# Crumb_Adapter_V1_2.net
KiCad netlist of a schematic drawn in EAGLE
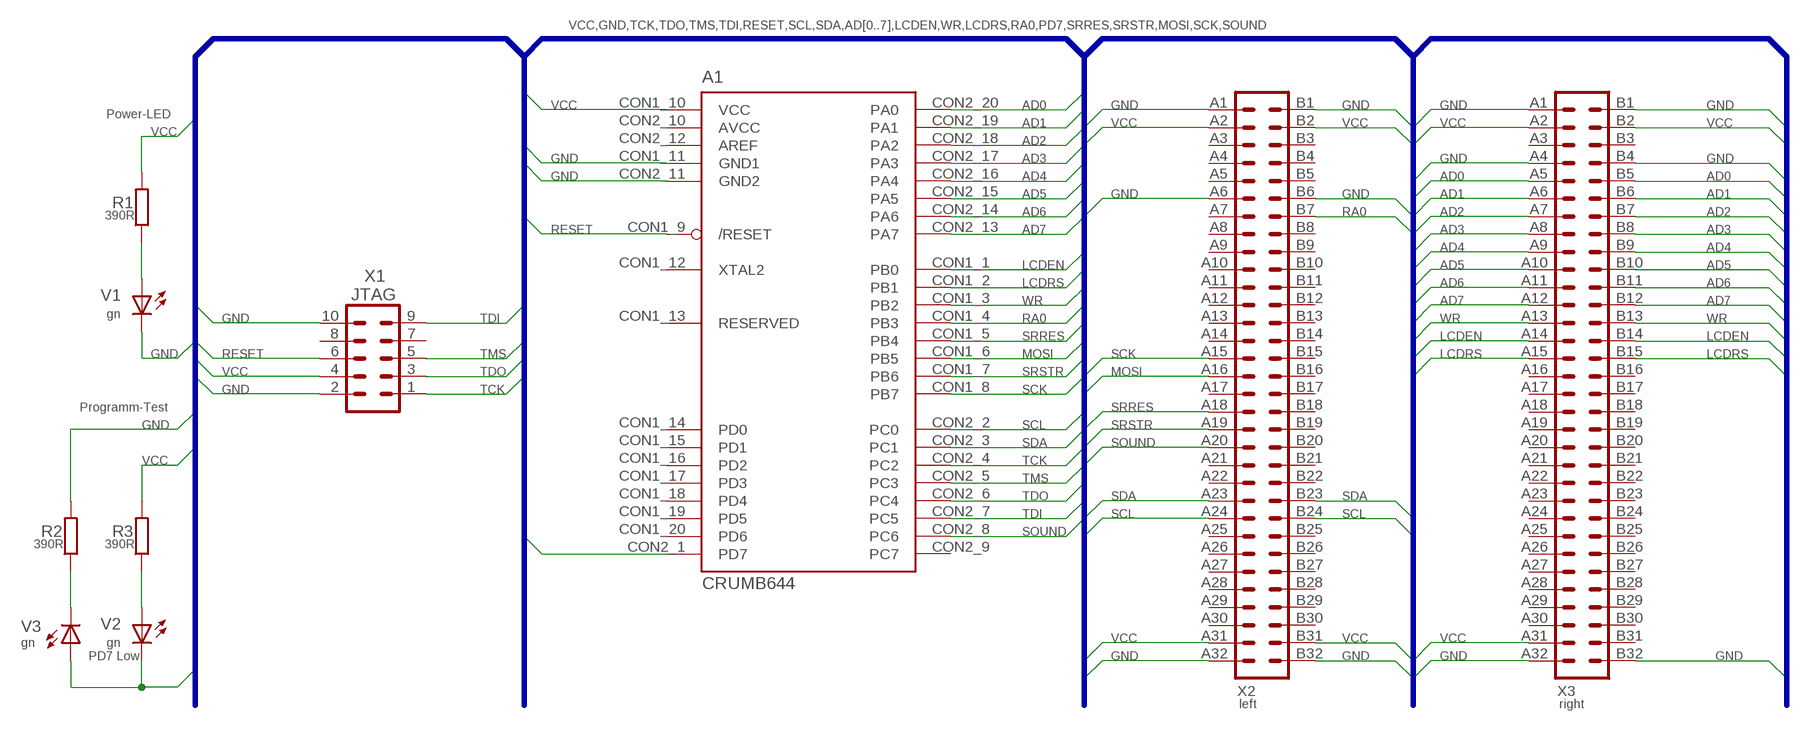
[diagram p0: schematic, sheet 1]

(export (version "E")
  (design (tool "Eeschema 10.0.6"))
  (components
    (comp (ref "A1")
      (value "CRUMB644")
      (footprint "eagle-import:CRUMB644")
      (libsource (lib "eagle-import") (part "CRUMB644"))
    )
    (comp (ref "R1")
      (value "390R")
      (footprint "eagle-import:M1206")
      (libsource (lib "eagle-import") (part "R-EU_VM1206"))
    )
    (comp (ref "R2")
      (value "390R")
      (footprint "eagle-import:M1206")
      (libsource (lib "eagle-import") (part "R-EU_VM1206"))
    )
    (comp (ref "R3")
      (value "390R")
      (footprint "eagle-import:M1206")
      (libsource (lib "eagle-import") (part "R-EU_VM1206"))
    )
    (comp (ref "V1")
      (value "gn")
      (footprint "eagle-import:CHIPLED_1206")
      (libsource (lib "eagle-import") (part "LEDCHIPLED_1206"))
    )
    (comp (ref "V2")
      (value "gn")
      (footprint "eagle-import:CHIPLED_1206")
      (libsource (lib "eagle-import") (part "LEDCHIPLED_1206"))
    )
    (comp (ref "V3")
      (value "gn")
      (footprint "eagle-import:CHIPLED_1206")
      (libsource (lib "eagle-import") (part "LEDCHIPLED_1206"))
    )
    (comp (ref "X1")
      (value "JTAG")
      (footprint "eagle-import:MA05-2")
      (libsource (lib "eagle-import") (part "MA05-2"))
    )
    (comp (ref "X2")
      (value "left")
      (footprint "eagle-import:MAB32-2")
      (libsource (lib "eagle-import") (part "MAB64"))
    )
    (comp (ref "X3")
      (value "right")
      (footprint "eagle-import:MAB32-2")
      (libsource (lib "eagle-import") (part "MAB64"))
    )
  )
  (nets
    (net (code "1") (name "/AD0") (class "Default")
      (node (ref "A1") (pin "CON2_20") (pinfunction "PA0_CON2_20") (pintype "bidirectional"))
      (node (ref "X3") (pin "A5") (pinfunction "A5_A5") (pintype "passive"))
      (node (ref "X3") (pin "B5") (pinfunction "B5_B5") (pintype "passive"))
    )
    (net (code "2") (name "/AD1") (class "Default")
      (node (ref "A1") (pin "CON2_19") (pinfunction "PA1_CON2_19") (pintype "bidirectional"))
      (node (ref "X3") (pin "A6") (pinfunction "A6_A6") (pintype "passive"))
      (node (ref "X3") (pin "B6") (pinfunction "B6_B6") (pintype "passive"))
    )
    (net (code "3") (name "/AD2") (class "Default")
      (node (ref "A1") (pin "CON2_18") (pinfunction "PA2_CON2_18") (pintype "bidirectional"))
      (node (ref "X3") (pin "A7") (pinfunction "A7_A7") (pintype "passive"))
      (node (ref "X3") (pin "B7") (pinfunction "B7_B7") (pintype "passive"))
    )
    (net (code "4") (name "/AD3") (class "Default")
      (node (ref "A1") (pin "CON2_17") (pinfunction "PA3_CON2_17") (pintype "bidirectional"))
      (node (ref "X3") (pin "A8") (pinfunction "A8_A8") (pintype "passive"))
      (node (ref "X3") (pin "B8") (pinfunction "B8_B8") (pintype "passive"))
    )
    (net (code "5") (name "/AD4") (class "Default")
      (node (ref "A1") (pin "CON2_16") (pinfunction "PA4_CON2_16") (pintype "bidirectional"))
      (node (ref "X3") (pin "A9") (pinfunction "A9_A9") (pintype "passive"))
      (node (ref "X3") (pin "B9") (pinfunction "B9_B9") (pintype "passive"))
    )
    (net (code "6") (name "/AD5") (class "Default")
      (node (ref "A1") (pin "CON2_15") (pinfunction "PA5_CON2_15") (pintype "bidirectional"))
      (node (ref "X3") (pin "A10") (pinfunction "A10_A10") (pintype "passive"))
      (node (ref "X3") (pin "B10") (pinfunction "B10_B10") (pintype "passive"))
    )
    (net (code "7") (name "/AD6") (class "Default")
      (node (ref "A1") (pin "CON2_14") (pinfunction "PA6_CON2_14") (pintype "bidirectional"))
      (node (ref "X3") (pin "A11") (pinfunction "A11_A11") (pintype "passive"))
      (node (ref "X3") (pin "B11") (pinfunction "B11_B11") (pintype "passive"))
    )
    (net (code "8") (name "/AD7") (class "Default")
      (node (ref "A1") (pin "CON2_13") (pinfunction "PA7_CON2_13") (pintype "bidirectional"))
      (node (ref "X3") (pin "A12") (pinfunction "A12_A12") (pintype "passive"))
      (node (ref "X3") (pin "B12") (pinfunction "B12_B12") (pintype "passive"))
    )
    (net (code "9") (name "/GND") (class "Default")
      (node (ref "A1") (pin "CON1_11") (pinfunction "GND1_CON1_11") (pintype "power_in"))
      (node (ref "A1") (pin "CON2_11") (pinfunction "GND2_CON2_11") (pintype "power_in"))
      (node (ref "R2") (pin "2") (pinfunction "2_2") (pintype "passive"))
      (node (ref "V1") (pin "C") (pinfunction "C_C") (pintype "passive"))
      (node (ref "X1") (pin "10") (pinfunction "10_10") (pintype "passive"))
      (node (ref "X1") (pin "2") (pinfunction "2_2") (pintype "passive"))
      (node (ref "X2") (pin "A1") (pinfunction "A1_A1") (pintype "passive"))
      (node (ref "X2") (pin "A32") (pinfunction "A32_A32") (pintype "passive"))
      (node (ref "X2") (pin "A6") (pinfunction "A6_A6") (pintype "passive"))
      (node (ref "X2") (pin "B1") (pinfunction "B1_B1") (pintype "passive"))
      (node (ref "X2") (pin "B32") (pinfunction "B32_B32") (pintype "passive"))
      (node (ref "X2") (pin "B6") (pinfunction "B6_B6") (pintype "passive"))
      (node (ref "X3") (pin "A1") (pinfunction "A1_A1") (pintype "passive"))
      (node (ref "X3") (pin "A32") (pinfunction "A32_A32") (pintype "passive"))
      (node (ref "X3") (pin "A4") (pinfunction "A4_A4") (pintype "passive"))
      (node (ref "X3") (pin "B1") (pinfunction "B1_B1") (pintype "passive"))
      (node (ref "X3") (pin "B32") (pinfunction "B32_B32") (pintype "passive"))
      (node (ref "X3") (pin "B4") (pinfunction "B4_B4") (pintype "passive"))
    )
    (net (code "10") (name "/LCDEN") (class "Default")
      (node (ref "A1") (pin "CON1_1") (pinfunction "PB0_CON1_1") (pintype "bidirectional"))
      (node (ref "X3") (pin "A14") (pinfunction "A14_A14") (pintype "passive"))
      (node (ref "X3") (pin "B14") (pinfunction "B14_B14") (pintype "passive"))
    )
    (net (code "11") (name "/LCDRS") (class "Default")
      (node (ref "A1") (pin "CON1_2") (pinfunction "PB1_CON1_2") (pintype "bidirectional"))
      (node (ref "X3") (pin "A15") (pinfunction "A15_A15") (pintype "passive"))
      (node (ref "X3") (pin "B15") (pinfunction "B15_B15") (pintype "passive"))
    )
    (net (code "12") (name "/MOSI") (class "Default")
      (node (ref "A1") (pin "CON1_6") (pinfunction "PB5_CON1_6") (pintype "bidirectional"))
      (node (ref "X2") (pin "A16") (pinfunction "A16_A16") (pintype "passive"))
    )
    (net (code "13") (name "/PD7") (class "Default")
      (node (ref "A1") (pin "CON2_1") (pinfunction "PD7_CON2_1") (pintype "bidirectional"))
      (node (ref "V2") (pin "C") (pinfunction "C_C") (pintype "passive"))
      (node (ref "V3") (pin "A") (pinfunction "A_A") (pintype "passive"))
    )
    (net (code "14") (name "/RA0") (class "Default")
      (node (ref "A1") (pin "CON1_4") (pinfunction "PB3_CON1_4") (pintype "bidirectional"))
      (node (ref "X2") (pin "B7") (pinfunction "B7_B7") (pintype "passive"))
    )
    (net (code "15") (name "/RESET") (class "Default")
      (node (ref "A1") (pin "CON1_9") (pinfunction "/RESET_CON1_9") (pintype "input"))
      (node (ref "X1") (pin "6") (pinfunction "6_6") (pintype "passive"))
    )
    (net (code "16") (name "/SCK") (class "Default")
      (node (ref "A1") (pin "CON1_8") (pinfunction "PB7_CON1_8") (pintype "bidirectional"))
      (node (ref "X2") (pin "A15") (pinfunction "A15_A15") (pintype "passive"))
    )
    (net (code "17") (name "/SCL") (class "Default")
      (node (ref "A1") (pin "CON2_2") (pinfunction "PC0_CON2_2") (pintype "bidirectional"))
      (node (ref "X2") (pin "A24") (pinfunction "A24_A24") (pintype "passive"))
      (node (ref "X2") (pin "B24") (pinfunction "B24_B24") (pintype "passive"))
    )
    (net (code "18") (name "/SDA") (class "Default")
      (node (ref "A1") (pin "CON2_3") (pinfunction "PC1_CON2_3") (pintype "bidirectional"))
      (node (ref "X2") (pin "A23") (pinfunction "A23_A23") (pintype "passive"))
      (node (ref "X2") (pin "B23") (pinfunction "B23_B23") (pintype "passive"))
    )
    (net (code "19") (name "/SOUND") (class "Default")
      (node (ref "A1") (pin "CON2_8") (pinfunction "PC6_CON2_8") (pintype "bidirectional"))
      (node (ref "X2") (pin "A20") (pinfunction "A20_A20") (pintype "passive"))
    )
    (net (code "20") (name "/SRRES") (class "Default")
      (node (ref "A1") (pin "CON1_5") (pinfunction "PB4_CON1_5") (pintype "bidirectional"))
      (node (ref "X2") (pin "A18") (pinfunction "A18_A18") (pintype "passive"))
    )
    (net (code "21") (name "/SRSTR") (class "Default")
      (node (ref "A1") (pin "CON1_7") (pinfunction "PB6_CON1_7") (pintype "bidirectional"))
      (node (ref "X2") (pin "A19") (pinfunction "A19_A19") (pintype "passive"))
    )
    (net (code "22") (name "/TCK") (class "Default")
      (node (ref "A1") (pin "CON2_4") (pinfunction "PC2_CON2_4") (pintype "bidirectional"))
      (node (ref "X1") (pin "1") (pinfunction "1_1") (pintype "passive"))
    )
    (net (code "23") (name "/TDI") (class "Default")
      (node (ref "A1") (pin "CON2_7") (pinfunction "PC5_CON2_7") (pintype "bidirectional"))
      (node (ref "X1") (pin "9") (pinfunction "9_9") (pintype "passive"))
    )
    (net (code "24") (name "/TDO") (class "Default")
      (node (ref "A1") (pin "CON2_6") (pinfunction "PC4_CON2_6") (pintype "bidirectional"))
      (node (ref "X1") (pin "3") (pinfunction "3_3") (pintype "passive"))
    )
    (net (code "25") (name "/TMS") (class "Default")
      (node (ref "A1") (pin "CON2_5") (pinfunction "PC3_CON2_5") (pintype "bidirectional"))
      (node (ref "X1") (pin "5") (pinfunction "5_5") (pintype "passive"))
    )
    (net (code "26") (name "/VCC") (class "Default")
      (node (ref "A1") (pin "CON1_10") (pinfunction "VCC_CON1_10") (pintype "power_in"))
      (node (ref "R1") (pin "2") (pinfunction "2_2") (pintype "passive"))
      (node (ref "R3") (pin "2") (pinfunction "2_2") (pintype "passive"))
      (node (ref "X1") (pin "4") (pinfunction "4_4") (pintype "passive"))
      (node (ref "X2") (pin "A2") (pinfunction "A2_A2") (pintype "passive"))
      (node (ref "X2") (pin "A31") (pinfunction "A31_A31") (pintype "passive"))
      (node (ref "X2") (pin "B2") (pinfunction "B2_B2") (pintype "passive"))
      (node (ref "X2") (pin "B31") (pinfunction "B31_B31") (pintype "passive"))
      (node (ref "X3") (pin "A2") (pinfunction "A2_A2") (pintype "passive"))
      (node (ref "X3") (pin "A31") (pinfunction "A31_A31") (pintype "passive"))
      (node (ref "X3") (pin "B2") (pinfunction "B2_B2") (pintype "passive"))
    )
    (net (code "27") (name "/WR") (class "Default")
      (node (ref "A1") (pin "CON1_3") (pinfunction "PB2_CON1_3") (pintype "bidirectional"))
      (node (ref "X3") (pin "A13") (pinfunction "A13_A13") (pintype "passive"))
      (node (ref "X3") (pin "B13") (pinfunction "B13_B13") (pintype "passive"))
    )
    (net (code "29") (name "Net-(R1-Pad1)") (class "Default")
      (node (ref "R1") (pin "1") (pinfunction "1_1") (pintype "passive"))
      (node (ref "V1") (pin "A") (pinfunction "A_A") (pintype "passive"))
    )
    (net (code "30") (name "Net-(R2-Pad1)") (class "Default")
      (node (ref "R2") (pin "1") (pinfunction "1_1") (pintype "passive"))
      (node (ref "V3") (pin "C") (pinfunction "C_C") (pintype "passive"))
    )
    (net (code "31") (name "Net-(R3-Pad1)") (class "Default")
      (node (ref "R3") (pin "1") (pinfunction "1_1") (pintype "passive"))
      (node (ref "V2") (pin "A") (pinfunction "A_A") (pintype "passive"))
    )
    (net (code "32") (name "unconnected-(A1-AREF-PadCON2_12)") (class "Default")
      (node (ref "A1") (pin "CON2_12") (pinfunction "AREF_CON2_12") (pintype "input"))
    )
    (net (code "33") (name "unconnected-(A1-AVCC-PadCON2_10)") (class "Default")
      (node (ref "A1") (pin "CON2_10") (pinfunction "AVCC_CON2_10") (pintype "input"))
    )
    (net (code "34") (name "unconnected-(A1-PC7-PadCON2_9)") (class "Default")
      (node (ref "A1") (pin "CON2_9") (pinfunction "PC7_CON2_9") (pintype "bidirectional"))
    )
    (net (code "35") (name "unconnected-(A1-PD0-PadCON1_14)") (class "Default")
      (node (ref "A1") (pin "CON1_14") (pinfunction "PD0_CON1_14") (pintype "bidirectional"))
    )
    (net (code "36") (name "unconnected-(A1-PD1-PadCON1_15)") (class "Default")
      (node (ref "A1") (pin "CON1_15") (pinfunction "PD1_CON1_15") (pintype "bidirectional"))
    )
    (net (code "37") (name "unconnected-(A1-PD2-PadCON1_16)") (class "Default")
      (node (ref "A1") (pin "CON1_16") (pinfunction "PD2_CON1_16") (pintype "bidirectional"))
    )
    (net (code "38") (name "unconnected-(A1-PD3-PadCON1_17)") (class "Default")
      (node (ref "A1") (pin "CON1_17") (pinfunction "PD3_CON1_17") (pintype "bidirectional"))
    )
    (net (code "39") (name "unconnected-(A1-PD4-PadCON1_18)") (class "Default")
      (node (ref "A1") (pin "CON1_18") (pinfunction "PD4_CON1_18") (pintype "bidirectional"))
    )
    (net (code "40") (name "unconnected-(A1-PD5-PadCON1_19)") (class "Default")
      (node (ref "A1") (pin "CON1_19") (pinfunction "PD5_CON1_19") (pintype "bidirectional"))
    )
    (net (code "41") (name "unconnected-(A1-PD6-PadCON1_20)") (class "Default")
      (node (ref "A1") (pin "CON1_20") (pinfunction "PD6_CON1_20") (pintype "bidirectional"))
    )
    (net (code "42") (name "unconnected-(A1-RESERVED-PadCON1_13)") (class "Default")
      (node (ref "A1") (pin "CON1_13") (pinfunction "RESERVED_CON1_13") (pintype "no_connect"))
    )
    (net (code "43") (name "unconnected-(A1-XTAL2-PadCON1_12)") (class "Default")
      (node (ref "A1") (pin "CON1_12") (pinfunction "XTAL2_CON1_12") (pintype "bidirectional"))
    )
    (net (code "44") (name "unconnected-(X1-Pad7)") (class "Default")
      (node (ref "X1") (pin "7") (pinfunction "7_7") (pintype "passive"))
    )
    (net (code "45") (name "unconnected-(X1-Pad8)") (class "Default")
      (node (ref "X1") (pin "8") (pinfunction "8_8") (pintype "passive"))
    )
    (net (code "46") (name "unconnected-(X2-PadA3)") (class "Default")
      (node (ref "X2") (pin "A3") (pinfunction "A3_A3") (pintype "passive"))
    )
    (net (code "47") (name "unconnected-(X2-PadA4)") (class "Default")
      (node (ref "X2") (pin "A4") (pinfunction "A4_A4") (pintype "passive"))
    )
    (net (code "48") (name "unconnected-(X2-PadA5)") (class "Default")
      (node (ref "X2") (pin "A5") (pinfunction "A5_A5") (pintype "passive"))
    )
    (net (code "49") (name "unconnected-(X2-PadA7)") (class "Default")
      (node (ref "X2") (pin "A7") (pinfunction "A7_A7") (pintype "passive"))
    )
    (net (code "50") (name "unconnected-(X2-PadA8)") (class "Default")
      (node (ref "X2") (pin "A8") (pinfunction "A8_A8") (pintype "passive"))
    )
    (net (code "51") (name "unconnected-(X2-PadA9)") (class "Default")
      (node (ref "X2") (pin "A9") (pinfunction "A9_A9") (pintype "passive"))
    )
    (net (code "52") (name "unconnected-(X2-PadA10)") (class "Default")
      (node (ref "X2") (pin "A10") (pinfunction "A10_A10") (pintype "passive"))
    )
    (net (code "53") (name "unconnected-(X2-PadA11)") (class "Default")
      (node (ref "X2") (pin "A11") (pinfunction "A11_A11") (pintype "passive"))
    )
    (net (code "54") (name "unconnected-(X2-PadA12)") (class "Default")
      (node (ref "X2") (pin "A12") (pinfunction "A12_A12") (pintype "passive"))
    )
    (net (code "55") (name "unconnected-(X2-PadA13)") (class "Default")
      (node (ref "X2") (pin "A13") (pinfunction "A13_A13") (pintype "passive"))
    )
    (net (code "56") (name "unconnected-(X2-PadA14)") (class "Default")
      (node (ref "X2") (pin "A14") (pinfunction "A14_A14") (pintype "passive"))
    )
    (net (code "57") (name "unconnected-(X2-PadA17)") (class "Default")
      (node (ref "X2") (pin "A17") (pinfunction "A17_A17") (pintype "passive"))
    )
    (net (code "58") (name "unconnected-(X2-PadA21)") (class "Default")
      (node (ref "X2") (pin "A21") (pinfunction "A21_A21") (pintype "passive"))
    )
    (net (code "59") (name "unconnected-(X2-PadA22)") (class "Default")
      (node (ref "X2") (pin "A22") (pinfunction "A22_A22") (pintype "passive"))
    )
    (net (code "60") (name "unconnected-(X2-PadA25)") (class "Default")
      (node (ref "X2") (pin "A25") (pinfunction "A25_A25") (pintype "passive"))
    )
    (net (code "61") (name "unconnected-(X2-PadA26)") (class "Default")
      (node (ref "X2") (pin "A26") (pinfunction "A26_A26") (pintype "passive"))
    )
    (net (code "62") (name "unconnected-(X2-PadA27)") (class "Default")
      (node (ref "X2") (pin "A27") (pinfunction "A27_A27") (pintype "passive"))
    )
    (net (code "63") (name "unconnected-(X2-PadA28)") (class "Default")
      (node (ref "X2") (pin "A28") (pinfunction "A28_A28") (pintype "passive"))
    )
    (net (code "64") (name "unconnected-(X2-PadA29)") (class "Default")
      (node (ref "X2") (pin "A29") (pinfunction "A29_A29") (pintype "passive"))
    )
    (net (code "65") (name "unconnected-(X2-PadA30)") (class "Default")
      (node (ref "X2") (pin "A30") (pinfunction "A30_A30") (pintype "passive"))
    )
    (net (code "66") (name "unconnected-(X2-PadB3)") (class "Default")
      (node (ref "X2") (pin "B3") (pinfunction "B3_B3") (pintype "passive"))
    )
    (net (code "67") (name "unconnected-(X2-PadB4)") (class "Default")
      (node (ref "X2") (pin "B4") (pinfunction "B4_B4") (pintype "passive"))
    )
    (net (code "68") (name "unconnected-(X2-PadB5)") (class "Default")
      (node (ref "X2") (pin "B5") (pinfunction "B5_B5") (pintype "passive"))
    )
    (net (code "69") (name "unconnected-(X2-PadB8)") (class "Default")
      (node (ref "X2") (pin "B8") (pinfunction "B8_B8") (pintype "passive"))
    )
    (net (code "70") (name "unconnected-(X2-PadB9)") (class "Default")
      (node (ref "X2") (pin "B9") (pinfunction "B9_B9") (pintype "passive"))
    )
    (net (code "71") (name "unconnected-(X2-PadB10)") (class "Default")
      (node (ref "X2") (pin "B10") (pinfunction "B10_B10") (pintype "passive"))
    )
    (net (code "72") (name "unconnected-(X2-PadB11)") (class "Default")
      (node (ref "X2") (pin "B11") (pinfunction "B11_B11") (pintype "passive"))
    )
    (net (code "73") (name "unconnected-(X2-PadB12)") (class "Default")
      (node (ref "X2") (pin "B12") (pinfunction "B12_B12") (pintype "passive"))
    )
    (net (code "74") (name "unconnected-(X2-PadB13)") (class "Default")
      (node (ref "X2") (pin "B13") (pinfunction "B13_B13") (pintype "passive"))
    )
    (net (code "75") (name "unconnected-(X2-PadB14)") (class "Default")
      (node (ref "X2") (pin "B14") (pinfunction "B14_B14") (pintype "passive"))
    )
    (net (code "76") (name "unconnected-(X2-PadB15)") (class "Default")
      (node (ref "X2") (pin "B15") (pinfunction "B15_B15") (pintype "passive"))
    )
    (net (code "77") (name "unconnected-(X2-PadB16)") (class "Default")
      (node (ref "X2") (pin "B16") (pinfunction "B16_B16") (pintype "passive"))
    )
    (net (code "78") (name "unconnected-(X2-PadB17)") (class "Default")
      (node (ref "X2") (pin "B17") (pinfunction "B17_B17") (pintype "passive"))
    )
    (net (code "79") (name "unconnected-(X2-PadB18)") (class "Default")
      (node (ref "X2") (pin "B18") (pinfunction "B18_B18") (pintype "passive"))
    )
    (net (code "80") (name "unconnected-(X2-PadB19)") (class "Default")
      (node (ref "X2") (pin "B19") (pinfunction "B19_B19") (pintype "passive"))
    )
    (net (code "81") (name "unconnected-(X2-PadB20)") (class "Default")
      (node (ref "X2") (pin "B20") (pinfunction "B20_B20") (pintype "passive"))
    )
    (net (code "82") (name "unconnected-(X2-PadB21)") (class "Default")
      (node (ref "X2") (pin "B21") (pinfunction "B21_B21") (pintype "passive"))
    )
    (net (code "83") (name "unconnected-(X2-PadB22)") (class "Default")
      (node (ref "X2") (pin "B22") (pinfunction "B22_B22") (pintype "passive"))
    )
    (net (code "84") (name "unconnected-(X2-PadB25)") (class "Default")
      (node (ref "X2") (pin "B25") (pinfunction "B25_B25") (pintype "passive"))
    )
    (net (code "85") (name "unconnected-(X2-PadB26)") (class "Default")
      (node (ref "X2") (pin "B26") (pinfunction "B26_B26") (pintype "passive"))
    )
    (net (code "86") (name "unconnected-(X2-PadB27)") (class "Default")
      (node (ref "X2") (pin "B27") (pinfunction "B27_B27") (pintype "passive"))
    )
    (net (code "87") (name "unconnected-(X2-PadB28)") (class "Default")
      (node (ref "X2") (pin "B28") (pinfunction "B28_B28") (pintype "passive"))
    )
    (net (code "88") (name "unconnected-(X2-PadB29)") (class "Default")
      (node (ref "X2") (pin "B29") (pinfunction "B29_B29") (pintype "passive"))
    )
    (net (code "89") (name "unconnected-(X2-PadB30)") (class "Default")
      (node (ref "X2") (pin "B30") (pinfunction "B30_B30") (pintype "passive"))
    )
    (net (code "90") (name "unconnected-(X3-PadA3)") (class "Default")
      (node (ref "X3") (pin "A3") (pinfunction "A3_A3") (pintype "passive"))
    )
    (net (code "91") (name "unconnected-(X3-PadA16)") (class "Default")
      (node (ref "X3") (pin "A16") (pinfunction "A16_A16") (pintype "passive"))
    )
    (net (code "92") (name "unconnected-(X3-PadA17)") (class "Default")
      (node (ref "X3") (pin "A17") (pinfunction "A17_A17") (pintype "passive"))
    )
    (net (code "93") (name "unconnected-(X3-PadA18)") (class "Default")
      (node (ref "X3") (pin "A18") (pinfunction "A18_A18") (pintype "passive"))
    )
    (net (code "94") (name "unconnected-(X3-PadA19)") (class "Default")
      (node (ref "X3") (pin "A19") (pinfunction "A19_A19") (pintype "passive"))
    )
    (net (code "95") (name "unconnected-(X3-PadA20)") (class "Default")
      (node (ref "X3") (pin "A20") (pinfunction "A20_A20") (pintype "passive"))
    )
    (net (code "96") (name "unconnected-(X3-PadA21)") (class "Default")
      (node (ref "X3") (pin "A21") (pinfunction "A21_A21") (pintype "passive"))
    )
    (net (code "97") (name "unconnected-(X3-PadA22)") (class "Default")
      (node (ref "X3") (pin "A22") (pinfunction "A22_A22") (pintype "passive"))
    )
    (net (code "98") (name "unconnected-(X3-PadA23)") (class "Default")
      (node (ref "X3") (pin "A23") (pinfunction "A23_A23") (pintype "passive"))
    )
    (net (code "99") (name "unconnected-(X3-PadA24)") (class "Default")
      (node (ref "X3") (pin "A24") (pinfunction "A24_A24") (pintype "passive"))
    )
    (net (code "100") (name "unconnected-(X3-PadA25)") (class "Default")
      (node (ref "X3") (pin "A25") (pinfunction "A25_A25") (pintype "passive"))
    )
    (net (code "101") (name "unconnected-(X3-PadA26)") (class "Default")
      (node (ref "X3") (pin "A26") (pinfunction "A26_A26") (pintype "passive"))
    )
    (net (code "102") (name "unconnected-(X3-PadA27)") (class "Default")
      (node (ref "X3") (pin "A27") (pinfunction "A27_A27") (pintype "passive"))
    )
    (net (code "103") (name "unconnected-(X3-PadA28)") (class "Default")
      (node (ref "X3") (pin "A28") (pinfunction "A28_A28") (pintype "passive"))
    )
    (net (code "104") (name "unconnected-(X3-PadA29)") (class "Default")
      (node (ref "X3") (pin "A29") (pinfunction "A29_A29") (pintype "passive"))
    )
    (net (code "105") (name "unconnected-(X3-PadA30)") (class "Default")
      (node (ref "X3") (pin "A30") (pinfunction "A30_A30") (pintype "passive"))
    )
    (net (code "106") (name "unconnected-(X3-PadB3)") (class "Default")
      (node (ref "X3") (pin "B3") (pinfunction "B3_B3") (pintype "passive"))
    )
    (net (code "107") (name "unconnected-(X3-PadB16)") (class "Default")
      (node (ref "X3") (pin "B16") (pinfunction "B16_B16") (pintype "passive"))
    )
    (net (code "108") (name "unconnected-(X3-PadB17)") (class "Default")
      (node (ref "X3") (pin "B17") (pinfunction "B17_B17") (pintype "passive"))
    )
    (net (code "109") (name "unconnected-(X3-PadB18)") (class "Default")
      (node (ref "X3") (pin "B18") (pinfunction "B18_B18") (pintype "passive"))
    )
    (net (code "110") (name "unconnected-(X3-PadB19)") (class "Default")
      (node (ref "X3") (pin "B19") (pinfunction "B19_B19") (pintype "passive"))
    )
    (net (code "111") (name "unconnected-(X3-PadB20)") (class "Default")
      (node (ref "X3") (pin "B20") (pinfunction "B20_B20") (pintype "passive"))
    )
    (net (code "112") (name "unconnected-(X3-PadB21)") (class "Default")
      (node (ref "X3") (pin "B21") (pinfunction "B21_B21") (pintype "passive"))
    )
    (net (code "113") (name "unconnected-(X3-PadB22)") (class "Default")
      (node (ref "X3") (pin "B22") (pinfunction "B22_B22") (pintype "passive"))
    )
    (net (code "114") (name "unconnected-(X3-PadB23)") (class "Default")
      (node (ref "X3") (pin "B23") (pinfunction "B23_B23") (pintype "passive"))
    )
    (net (code "115") (name "unconnected-(X3-PadB24)") (class "Default")
      (node (ref "X3") (pin "B24") (pinfunction "B24_B24") (pintype "passive"))
    )
    (net (code "116") (name "unconnected-(X3-PadB25)") (class "Default")
      (node (ref "X3") (pin "B25") (pinfunction "B25_B25") (pintype "passive"))
    )
    (net (code "117") (name "unconnected-(X3-PadB26)") (class "Default")
      (node (ref "X3") (pin "B26") (pinfunction "B26_B26") (pintype "passive"))
    )
    (net (code "118") (name "unconnected-(X3-PadB27)") (class "Default")
      (node (ref "X3") (pin "B27") (pinfunction "B27_B27") (pintype "passive"))
    )
    (net (code "119") (name "unconnected-(X3-PadB28)") (class "Default")
      (node (ref "X3") (pin "B28") (pinfunction "B28_B28") (pintype "passive"))
    )
    (net (code "120") (name "unconnected-(X3-PadB29)") (class "Default")
      (node (ref "X3") (pin "B29") (pinfunction "B29_B29") (pintype "passive"))
    )
    (net (code "121") (name "unconnected-(X3-PadB30)") (class "Default")
      (node (ref "X3") (pin "B30") (pinfunction "B30_B30") (pintype "passive"))
    )
    (net (code "122") (name "unconnected-(X3-PadB31)") (class "Default")
      (node (ref "X3") (pin "B31") (pinfunction "B31_B31") (pintype "passive"))
    )
  )
)
